# Controller_Board.net
KiCad netlist of a schematic drawn in Altium Designer
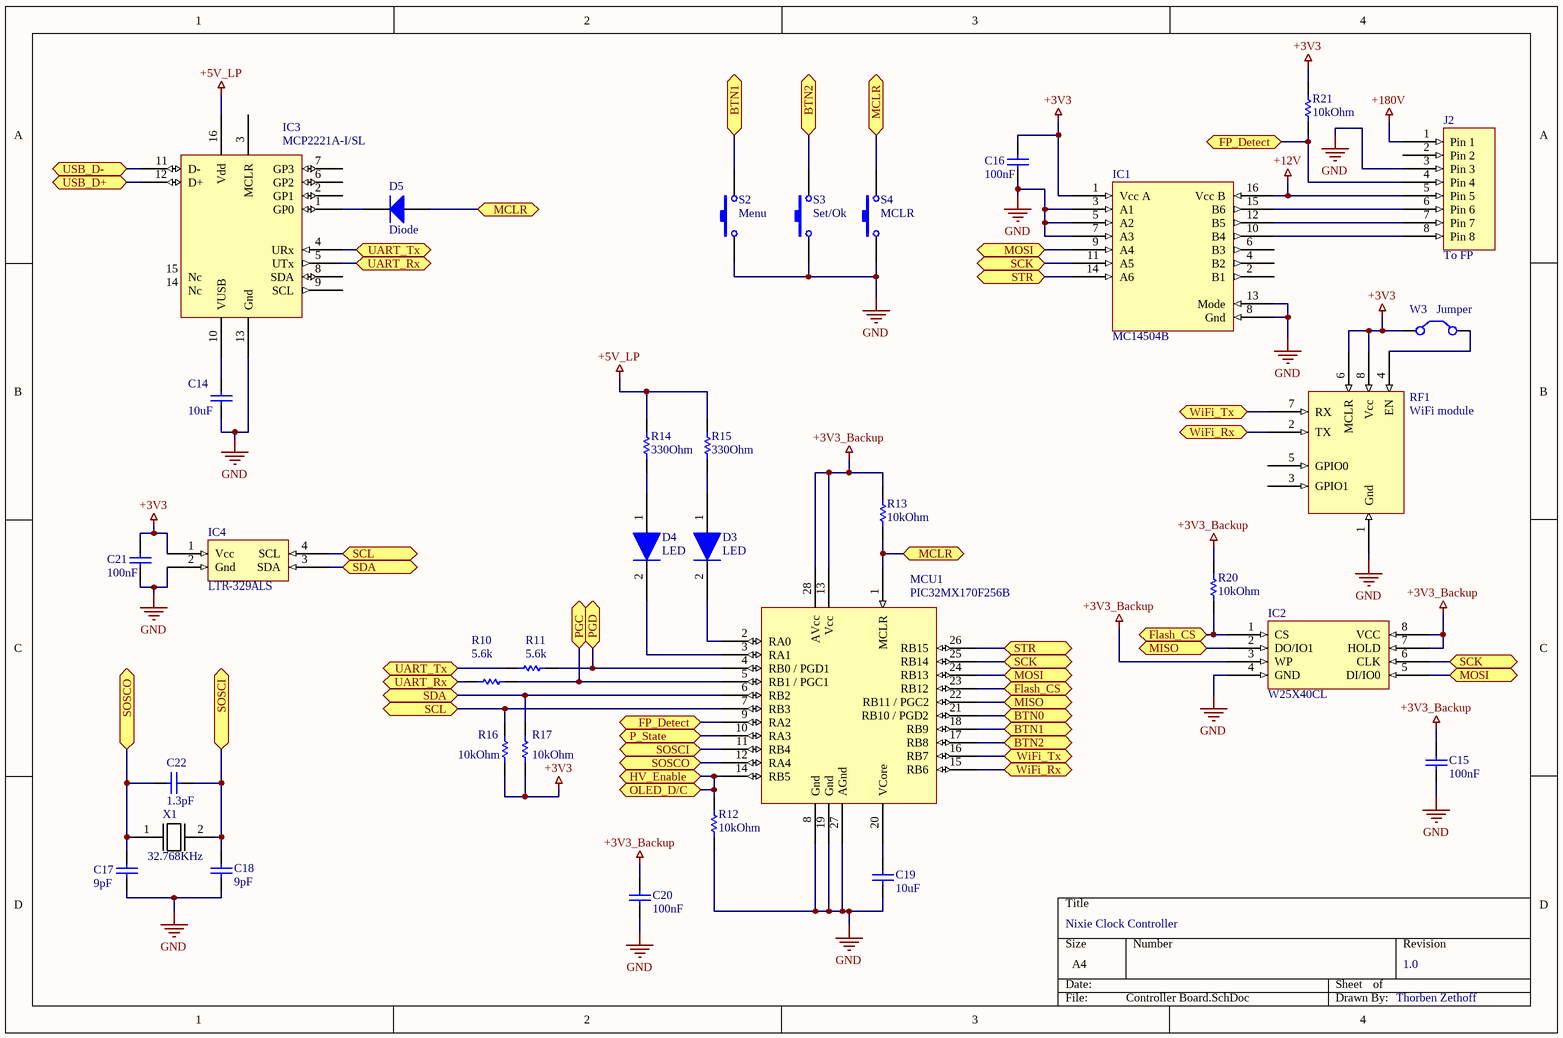
[diagram p0: Controller Board.SchDoc]

(export (version "E")
  (design (tool "Eeschema 10.0.6"))
  (components
    (comp (ref "C14")
      (value "10uF")
      (footprint "0603")
      (description "Capacitor")
      (fields (field (name "PUBLISHER") "Altium Limited"))
      (libsource (lib "Miscellaneous Devices") (part "Cap"))
    )
    (comp (ref "C15")
      (value "100nF")
      (footprint "0603")
      (description "Capacitor")
      (fields (field (name "PUBLISHER") "Altium Limited"))
      (libsource (lib "Miscellaneous Devices") (part "Cap"))
    )
    (comp (ref "C16")
      (value "100nF")
      (footprint "0603")
      (description "Capacitor")
      (fields (field (name "PUBLISHER") "Altium Limited"))
      (libsource (lib "Miscellaneous Devices") (part "Cap"))
    )
    (comp (ref "C17")
      (value "9pF")
      (footprint "0603")
      (description "Capacitor")
      (fields (field (name "PUBLISHER") "Altium Limited"))
      (libsource (lib "Miscellaneous Devices") (part "Cap"))
    )
    (comp (ref "C18")
      (value "9pF")
      (footprint "0603")
      (description "Capacitor")
      (fields (field (name "PUBLISHER") "Altium Limited"))
      (libsource (lib "Miscellaneous Devices") (part "Cap"))
    )
    (comp (ref "C19")
      (value "10uF")
      (footprint "0603")
      (description "Capacitor")
      (fields (field (name "PUBLISHER") "Altium Limited"))
      (libsource (lib "Miscellaneous Devices") (part "Cap"))
    )
    (comp (ref "C20")
      (value "100nF")
      (footprint "0603")
      (description "Capacitor")
      (fields (field (name "PUBLISHER") "Altium Limited"))
      (libsource (lib "Miscellaneous Devices") (part "Cap"))
    )
    (comp (ref "C21")
      (value "100nF")
      (footprint "0603")
      (description "Capacitor")
      (fields (field (name "PUBLISHER") "Altium Limited"))
      (libsource (lib "Miscellaneous Devices") (part "Cap"))
    )
    (comp (ref "C22")
      (value "1.3pF")
      (footprint "0603")
      (description "Capacitor")
      (fields (field (name "PUBLISHER") "Altium Limited"))
      (libsource (lib "Miscellaneous Devices") (part "Cap"))
    )
    (comp (ref "D3") (value "LED") (footprint "0603") (libsource (lib "stdLib") (part "LED")))
    (comp (ref "D4") (value "LED") (footprint "0603") (libsource (lib "stdLib") (part "LED")))
    (comp (ref "D5")
      (value "Diode")
      (footprint "SOD523")
      (description "Default Diode")
      (fields (field (name "PUBLISHER") "Altium Limited"))
      (libsource (lib "Miscellaneous Devices") (part "Diode"))
    )
    (comp (ref "IC1")
      (value "MC14504B")
      (footprint "TSSOP16")
      (description "6ch Level shifter")
      (libsource (lib "stdLib") (part "MC14504B"))
    )
    (comp (ref "IC2") (value "W25X40CL") (footprint "SOIC8") (libsource (lib "stdLib") (part "W25X40CL")))
    (comp (ref "IC3")
      (value "MCP2221A-I/SL")
      (footprint "QFN16 4x4")
      (description "USB to Uart/I2C Converter")
      (libsource (lib "stdLib") (part "MCP2221A-I/SL"))
    )
    (comp (ref "IC4")
      (value "‎LTR-329ALS")
      (footprint "4DFN")
      (description "Ambient light sensor with ADC")
      (libsource (lib "stdLib") (part "‎LTR-329ALS"))
    )
    (comp (ref "J2")
      (value "To FP")
      (footprint "Molex 0528080871")
      (description "8 Pin FFC SMD staight")
      (libsource (lib "stdLib") (part "Molex 0528080871"))
    )
    (comp (ref "MCU1")
      (value "PIC32MX170F256B")
      (footprint "TSSOP28_Wide")
      (libsource (lib "stdLib") (part "PIC32MX1xxFxxxB"))
    )
    (comp (ref "R10")
      (value "5.6k")
      (footprint "0805")
      (fields (field (name "PUBLISHER") "Altium Limited"))
      (libsource (lib "Miscellaneous Devices") (part "Res1"))
    )
    (comp (ref "R11")
      (value "5.6k")
      (footprint "0805")
      (fields (field (name "PUBLISHER") "Altium Limited"))
      (libsource (lib "Miscellaneous Devices") (part "Res1"))
    )
    (comp (ref "R12")
      (value "10kOhm")
      (footprint "0603")
      (description "Resistor")
      (fields (field (name "PUBLISHER") "Altium Limited"))
      (libsource (lib "Miscellaneous Devices") (part "Res1"))
    )
    (comp (ref "R13")
      (value "10kOhm")
      (footprint "0603")
      (description "Resistor")
      (fields (field (name "PUBLISHER") "Altium Limited"))
      (libsource (lib "Miscellaneous Devices") (part "Res1"))
    )
    (comp (ref "R14")
      (value "330Ohm")
      (footprint "0603")
      (description "Resistor")
      (fields (field (name "PUBLISHER") "Altium Limited"))
      (libsource (lib "Miscellaneous Devices") (part "Res1"))
    )
    (comp (ref "R15")
      (value "330Ohm")
      (footprint "0603")
      (description "Resistor")
      (fields (field (name "PUBLISHER") "Altium Limited"))
      (libsource (lib "Miscellaneous Devices") (part "Res1"))
    )
    (comp (ref "R16")
      (value "10kOhm")
      (footprint "0603")
      (description "Resistor")
      (fields (field (name "PUBLISHER") "Altium Limited"))
      (libsource (lib "Miscellaneous Devices") (part "Res1"))
    )
    (comp (ref "R17")
      (value "10kOhm")
      (footprint "0603")
      (description "Resistor")
      (fields (field (name "PUBLISHER") "Altium Limited"))
      (libsource (lib "Miscellaneous Devices") (part "Res1"))
    )
    (comp (ref "R20")
      (value "10kOhm")
      (footprint "0603")
      (description "Resistor")
      (fields (field (name "PUBLISHER") "Altium Limited"))
      (libsource (lib "Miscellaneous Devices") (part "Res1"))
    )
    (comp (ref "R21")
      (value "10kOhm")
      (footprint "0603")
      (description "Resistor")
      (fields (field (name "PUBLISHER") "Altium Limited"))
      (libsource (lib "Miscellaneous Devices") (part "Res1"))
    )
    (comp (ref "RF1")
      (value "WiFi module")
      (footprint "EPS8266 Module")
      (libsource (lib "stdLib") (part "ESP8266"))
    )
    (comp (ref "S2")
      (value "Menu")
      (footprint "EVQP7XXX")
      (description "Switch")
      (fields (field (name "PUBLISHER") "Altium Limited"))
      (libsource (lib "Miscellaneous Devices") (part "SW-PB"))
    )
    (comp (ref "S3")
      (value "Set/Ok")
      (footprint "EVQP7XXX")
      (description "Switch")
      (fields (field (name "PUBLISHER") "Altium Limited"))
      (libsource (lib "Miscellaneous Devices") (part "SW-PB"))
    )
    (comp (ref "S4")
      (value "MCLR")
      (footprint "EVQP7XXX")
      (fields (field (name "PUBLISHER") "Altium Limited"))
      (libsource (lib "Miscellaneous Devices") (part "SW-PB"))
    )
    (comp (ref "W3")
      (value "Jumper")
      (footprint "Solder Jumper")
      (description "I2C Passthrough")
      (fields (field (name "PUBLISHER") "Altium Limited"))
      (libsource (lib "Miscellaneous Devices") (part "Jumper"))
    )
    (comp (ref "X1")
      (value "32.768KHz")
      (footprint "2-SMD, Quartz")
      (libsource (lib "stdLib") (part "Tuning fork crystal"))
    )
  )
  (nets
    (net (code "1") (name "+3V3") (class "Default")
      (node (ref "C16") (pin "1") (pinfunction "1_1") (pintype "passive"))
      (node (ref "C21") (pin "1") (pinfunction "1_1") (pintype "passive"))
      (node (ref "IC1") (pin "1") (pinfunction "Vcc_A_1") (pintype "input"))
      (node (ref "IC4") (pin "1") (pinfunction "Vcc_1") (pintype "input"))
      (node (ref "R16") (pin "1") (pinfunction "1_1") (pintype "passive"))
      (node (ref "R17") (pin "1") (pinfunction "1_1") (pintype "passive"))
      (node (ref "R21") (pin "2") (pinfunction "2_2") (pintype "passive"))
      (node (ref "RF1") (pin "6") (pinfunction "MCLR_6") (pintype "input"))
      (node (ref "RF1") (pin "8") (pinfunction "Vcc_8") (pintype "input"))
      (node (ref "W3") (pin "1") (pinfunction "C1_1") (pintype "passive"))
    )
    (net (code "2") (name "+3V3_Backup") (class "Default")
      (node (ref "C15") (pin "1") (pinfunction "1_1") (pintype "passive"))
      (node (ref "C20") (pin "1") (pinfunction "1_1") (pintype "passive"))
      (node (ref "IC2") (pin "3") (pinfunction "WP_3") (pintype "input"))
      (node (ref "IC2") (pin "7") (pinfunction "HOLD_7") (pintype "input"))
      (node (ref "IC2") (pin "8") (pinfunction "VCC_8") (pintype "input"))
      (node (ref "MCU1") (pin "13") (pinfunction "Vcc_13") (pintype "power_in"))
      (node (ref "MCU1") (pin "28") (pinfunction "AVcc_28") (pintype "power_in"))
      (node (ref "R13") (pin "2") (pinfunction "2_2") (pintype "passive"))
      (node (ref "R20") (pin "2") (pinfunction "2_2") (pintype "passive"))
    )
    (net (code "3") (name "+5V_LP") (class "Default")
      (node (ref "IC3") (pin "16") (pinfunction "Vdd_16") (pintype "power_in"))
      (node (ref "R14") (pin "2") (pinfunction "2_2") (pintype "passive"))
      (node (ref "R15") (pin "1") (pinfunction "1_1") (pintype "passive"))
    )
    (net (code "4") (name "+12V") (class "Default")
      (node (ref "IC1") (pin "16") (pinfunction "Vcc_B_16") (pintype "input"))
      (node (ref "J2") (pin "5") (pinfunction "Pin_5_5") (pintype "input"))
    )
    (net (code "5") (name "+180V") (class "Default")
      (node (ref "J2") (pin "1") (pinfunction "Pin_1_1") (pintype "input"))
    )
    (net (code "6") (name "/BTN0") (class "Default")
      (node (ref "MCU1") (pin "21") (pinfunction "RB10_/_PGD2_21") (pintype "bidirectional"))
    )
    (net (code "7") (name "/BTN1") (class "Default")
      (node (ref "MCU1") (pin "18") (pinfunction "RB9_18") (pintype "bidirectional"))
      (node (ref "S2") (pin "2") (pinfunction "2_2") (pintype "passive"))
    )
    (net (code "8") (name "/BTN2") (class "Default")
      (node (ref "MCU1") (pin "17") (pinfunction "RB8_17") (pintype "bidirectional"))
      (node (ref "S3") (pin "2") (pinfunction "2_2") (pintype "passive"))
    )
    (net (code "9") (name "/FP_Detect") (class "Default")
      (node (ref "J2") (pin "4") (pinfunction "Pin_4_4") (pintype "input"))
      (node (ref "MCU1") (pin "9") (pinfunction "RA2_9") (pintype "bidirectional"))
      (node (ref "R21") (pin "1") (pinfunction "1_1") (pintype "passive"))
    )
    (net (code "10") (name "/Flash_CS") (class "Default")
      (node (ref "IC2") (pin "1") (pinfunction "CS_1") (pintype "input"))
      (node (ref "MCU1") (pin "23") (pinfunction "RB12_23") (pintype "bidirectional"))
      (node (ref "R20") (pin "1") (pinfunction "1_1") (pintype "passive"))
    )
    (net (code "11") (name "/HV_Enable") (class "Default")
      (node (ref "MCU1") (pin "14") (pinfunction "RB5_14") (pintype "bidirectional"))
      (node (ref "R12") (pin "2") (pinfunction "2_2") (pintype "passive"))
    )
    (net (code "12") (name "/MCLR") (class "Default")
      (node (ref "D5") (pin "1") (pinfunction "A_1") (pintype "passive"))
      (node (ref "MCU1") (pin "1") (pinfunction "MCLR_1") (pintype "input"))
      (node (ref "R13") (pin "1") (pinfunction "1_1") (pintype "passive"))
      (node (ref "S4") (pin "2") (pinfunction "2_2") (pintype "passive"))
    )
    (net (code "13") (name "/MISO") (class "Default")
      (node (ref "IC2") (pin "2") (pinfunction "DO/IO1_2") (pintype "input"))
      (node (ref "MCU1") (pin "22") (pinfunction "RB11_/_PGC2_22") (pintype "bidirectional"))
    )
    (net (code "14") (name "/MOSI") (class "Default")
      (node (ref "IC1") (pin "9") (pinfunction "A4_9") (pintype "input"))
      (node (ref "IC2") (pin "5") (pinfunction "DI/IO0_5") (pintype "input"))
      (node (ref "MCU1") (pin "24") (pinfunction "RB13_24") (pintype "bidirectional"))
    )
    (net (code "15") (name "/PGC") (class "Default")
      (node (ref "MCU1") (pin "5") (pinfunction "RB1_/_PGC1_5") (pintype "bidirectional"))
      (node (ref "R10") (pin "2") (pinfunction "2_2") (pintype "passive"))
    )
    (net (code "16") (name "/PGD") (class "Default")
      (node (ref "MCU1") (pin "4") (pinfunction "RB0_/_PGD1_4") (pintype "bidirectional"))
      (node (ref "R11") (pin "1") (pinfunction "1_1") (pintype "passive"))
    )
    (net (code "17") (name "/P_State") (class "Default")
      (node (ref "MCU1") (pin "10") (pinfunction "RA3_10") (pintype "bidirectional"))
    )
    (net (code "18") (name "/SCK") (class "Default")
      (node (ref "IC1") (pin "11") (pinfunction "A5_11") (pintype "input"))
      (node (ref "IC2") (pin "6") (pinfunction "CLK_6") (pintype "input"))
      (node (ref "MCU1") (pin "25") (pinfunction "RB14_25") (pintype "bidirectional"))
    )
    (net (code "19") (name "/SCL") (class "Default")
      (node (ref "IC4") (pin "4") (pinfunction "SCL_4") (pintype "input"))
      (node (ref "MCU1") (pin "7") (pinfunction "RB3_7") (pintype "bidirectional"))
      (node (ref "R16") (pin "2") (pinfunction "2_2") (pintype "passive"))
    )
    (net (code "20") (name "/SDA") (class "Default")
      (node (ref "IC4") (pin "3") (pinfunction "SDA_3") (pintype "input"))
      (node (ref "MCU1") (pin "6") (pinfunction "RB2_6") (pintype "bidirectional"))
      (node (ref "R17") (pin "2") (pinfunction "2_2") (pintype "passive"))
    )
    (net (code "21") (name "/SOSCI") (class "Default")
      (node (ref "C18") (pin "1") (pinfunction "1_1") (pintype "passive"))
      (node (ref "C22") (pin "2") (pinfunction "2_2") (pintype "passive"))
      (node (ref "MCU1") (pin "11") (pinfunction "RB4_11") (pintype "bidirectional"))
      (node (ref "X1") (pin "2") (pintype "passive"))
    )
    (net (code "22") (name "/SOSCO") (class "Default")
      (node (ref "C17") (pin "1") (pinfunction "1_1") (pintype "passive"))
      (node (ref "C22") (pin "1") (pinfunction "1_1") (pintype "passive"))
      (node (ref "MCU1") (pin "12") (pinfunction "RA4_12") (pintype "bidirectional"))
      (node (ref "X1") (pin "1") (pintype "passive"))
    )
    (net (code "23") (name "/STR") (class "Default")
      (node (ref "IC1") (pin "14") (pinfunction "A6_14") (pintype "input"))
      (node (ref "MCU1") (pin "26") (pinfunction "RB15_26") (pintype "bidirectional"))
    )
    (net (code "24") (name "/UART_Rx") (class "Default")
      (node (ref "IC3") (pin "5") (pinfunction "UTx_5") (pintype "output"))
      (node (ref "R10") (pin "1") (pinfunction "1_1") (pintype "passive"))
    )
    (net (code "25") (name "/UART_Tx") (class "Default")
      (node (ref "IC3") (pin "4") (pinfunction "URx_4") (pintype "input"))
      (node (ref "R11") (pin "2") (pinfunction "2_2") (pintype "passive"))
    )
    (net (code "26") (name "/USB_D+") (class "Default")
      (node (ref "IC3") (pin "12") (pinfunction "D+_12") (pintype "bidirectional"))
    )
    (net (code "27") (name "/USB_D-") (class "Default")
      (node (ref "IC3") (pin "11") (pinfunction "D-_11") (pintype "bidirectional"))
    )
    (net (code "28") (name "/WiFi_Rx") (class "Default")
      (node (ref "MCU1") (pin "15") (pinfunction "RB6_15") (pintype "bidirectional"))
      (node (ref "RF1") (pin "2") (pinfunction "TX_2") (pintype "input"))
    )
    (net (code "29") (name "/WiFi_Tx") (class "Default")
      (node (ref "MCU1") (pin "16") (pinfunction "RB7_16") (pintype "bidirectional"))
      (node (ref "RF1") (pin "7") (pinfunction "RX_7") (pintype "input"))
    )
    (net (code "30") (name "GND") (class "Default")
      (node (ref "C14") (pin "2") (pinfunction "2_2") (pintype "passive"))
      (node (ref "C15") (pin "2") (pinfunction "2_2") (pintype "passive"))
      (node (ref "C16") (pin "2") (pinfunction "2_2") (pintype "passive"))
      (node (ref "C17") (pin "2") (pinfunction "2_2") (pintype "passive"))
      (node (ref "C18") (pin "2") (pinfunction "2_2") (pintype "passive"))
      (node (ref "C19") (pin "2") (pinfunction "2_2") (pintype "passive"))
      (node (ref "C20") (pin "2") (pinfunction "2_2") (pintype "passive"))
      (node (ref "C21") (pin "2") (pinfunction "2_2") (pintype "passive"))
      (node (ref "IC1") (pin "13") (pinfunction "Mode_13") (pintype "input"))
      (node (ref "IC1") (pin "3") (pinfunction "A1_3") (pintype "input"))
      (node (ref "IC1") (pin "5") (pinfunction "A2_5") (pintype "input"))
      (node (ref "IC1") (pin "7") (pinfunction "A3_7") (pintype "input"))
      (node (ref "IC1") (pin "8") (pinfunction "Gnd_8") (pintype "input"))
      (node (ref "IC2") (pin "4") (pinfunction "GND_4") (pintype "input"))
      (node (ref "IC3") (pin "13") (pinfunction "Gnd_13") (pintype "power_in"))
      (node (ref "IC4") (pin "2") (pinfunction "Gnd_2") (pintype "input"))
      (node (ref "J2") (pin "3") (pinfunction "Pin_3_3") (pintype "input"))
      (node (ref "MCU1") (pin "19") (pinfunction "Gnd_19") (pintype "power_in"))
      (node (ref "MCU1") (pin "27") (pinfunction "AGnd_27") (pintype "power_in"))
      (node (ref "MCU1") (pin "8") (pinfunction "Gnd_8") (pintype "power_in"))
      (node (ref "R12") (pin "1") (pinfunction "1_1") (pintype "passive"))
      (node (ref "RF1") (pin "1") (pinfunction "Gnd_1") (pintype "input"))
      (node (ref "S2") (pin "1") (pinfunction "1_1") (pintype "passive"))
      (node (ref "S3") (pin "1") (pinfunction "1_1") (pintype "passive"))
      (node (ref "S4") (pin "1") (pinfunction "1_1") (pintype "passive"))
    )
    (net (code "31") (name "Net-(D3-Pad1)") (class "Default")
      (node (ref "D3") (pin "1") (pintype "passive"))
      (node (ref "R15") (pin "2") (pinfunction "2_2") (pintype "passive"))
    )
    (net (code "32") (name "Net-(D4-Pad1)") (class "Default")
      (node (ref "D4") (pin "1") (pintype "passive"))
      (node (ref "R14") (pin "1") (pinfunction "1_1") (pintype "passive"))
    )
    (net (code "33") (name "Net-(D5-K)") (class "Default")
      (node (ref "D5") (pin "2") (pinfunction "K_2") (pintype "passive"))
      (node (ref "IC3") (pin "1") (pinfunction "GP0_1") (pintype "bidirectional"))
    )
    (net (code "34") (name "Net-(IC1-B4)") (class "Default")
      (node (ref "IC1") (pin "10") (pinfunction "B4_10") (pintype "output"))
      (node (ref "J2") (pin "8") (pinfunction "Pin_8_8") (pintype "input"))
    )
    (net (code "35") (name "Net-(IC1-B5)") (class "Default")
      (node (ref "IC1") (pin "12") (pinfunction "B5_12") (pintype "output"))
      (node (ref "J2") (pin "7") (pinfunction "Pin_7_7") (pintype "input"))
    )
    (net (code "36") (name "Net-(IC1-B6)") (class "Default")
      (node (ref "IC1") (pin "15") (pinfunction "B6_15") (pintype "output"))
      (node (ref "J2") (pin "6") (pinfunction "Pin_6_6") (pintype "input"))
    )
    (net (code "37") (name "Net-(IC3-VUSB)") (class "Default")
      (node (ref "C14") (pin "1") (pinfunction "1_1") (pintype "passive"))
      (node (ref "IC3") (pin "10") (pinfunction "VUSB_10") (pintype "power_in"))
    )
    (net (code "38") (name "Net-(MCU1-RA0)") (class "Default")
      (node (ref "D3") (pin "2") (pintype "passive"))
      (node (ref "MCU1") (pin "2") (pinfunction "RA0_2") (pintype "bidirectional"))
    )
    (net (code "39") (name "Net-(MCU1-RA1)") (class "Default")
      (node (ref "D4") (pin "2") (pintype "passive"))
      (node (ref "MCU1") (pin "3") (pinfunction "RA1_3") (pintype "bidirectional"))
    )
    (net (code "40") (name "Net-(MCU1-VCore)") (class "Default")
      (node (ref "C19") (pin "1") (pinfunction "1_1") (pintype "passive"))
      (node (ref "MCU1") (pin "20") (pinfunction "VCore_20") (pintype "power_in"))
    )
    (net (code "41") (name "Net-(RF1-EN)") (class "Default")
      (node (ref "RF1") (pin "4") (pinfunction "EN_4") (pintype "input"))
      (node (ref "W3") (pin "2") (pinfunction "C2_2") (pintype "passive"))
    )
    (net (code "42") (name "unconnected-(IC1-B1-Pad2)") (class "Default")
      (node (ref "IC1") (pin "2") (pinfunction "B1_2") (pintype "output"))
    )
    (net (code "43") (name "unconnected-(IC1-B2-Pad4)") (class "Default")
      (node (ref "IC1") (pin "4") (pinfunction "B2_4") (pintype "output"))
    )
    (net (code "44") (name "unconnected-(IC1-B3-Pad6)") (class "Default")
      (node (ref "IC1") (pin "6") (pinfunction "B3_6") (pintype "output"))
    )
    (net (code "45") (name "unconnected-(IC3-GP1-Pad2)") (class "Default")
      (node (ref "IC3") (pin "2") (pinfunction "GP1_2") (pintype "bidirectional"))
    )
    (net (code "46") (name "unconnected-(IC3-GP2-Pad6)") (class "Default")
      (node (ref "IC3") (pin "6") (pinfunction "GP2_6") (pintype "bidirectional"))
    )
    (net (code "47") (name "unconnected-(IC3-GP3-Pad7)") (class "Default")
      (node (ref "IC3") (pin "7") (pinfunction "GP3_7") (pintype "bidirectional"))
    )
    (net (code "48") (name "unconnected-(IC3-MCLR-Pad3)") (class "Default")
      (node (ref "IC3") (pin "3") (pinfunction "MCLR_3") (pintype "passive"))
    )
    (net (code "49") (name "unconnected-(IC3-Nc-Pad14)") (class "Default")
      (node (ref "IC3") (pin "14") (pinfunction "Nc_14") (pintype "passive"))
    )
    (net (code "50") (name "unconnected-(IC3-Nc-Pad15)") (class "Default")
      (node (ref "IC3") (pin "15") (pinfunction "Nc_15") (pintype "passive"))
    )
    (net (code "51") (name "unconnected-(IC3-SCL-Pad9)") (class "Default")
      (node (ref "IC3") (pin "9") (pinfunction "SCL_9") (pintype "output"))
    )
    (net (code "52") (name "unconnected-(IC3-SDA-Pad8)") (class "Default")
      (node (ref "IC3") (pin "8") (pinfunction "SDA_8") (pintype "bidirectional"))
    )
    (net (code "53") (name "unconnected-(J2-Pin_2-Pad2)") (class "Default")
      (node (ref "J2") (pin "2") (pinfunction "Pin_2_2") (pintype "input"))
    )
    (net (code "54") (name "unconnected-(RF1-GPIO0-Pad5)") (class "Default")
      (node (ref "RF1") (pin "5") (pinfunction "GPIO0_5") (pintype "input"))
    )
    (net (code "55") (name "unconnected-(RF1-GPIO1-Pad3)") (class "Default")
      (node (ref "RF1") (pin "3") (pinfunction "GPIO1_3") (pintype "input"))
    )
  )
)
